# Schematic_2023-04-17.net
KiCad netlist of a schematic drawn in Altium Designer
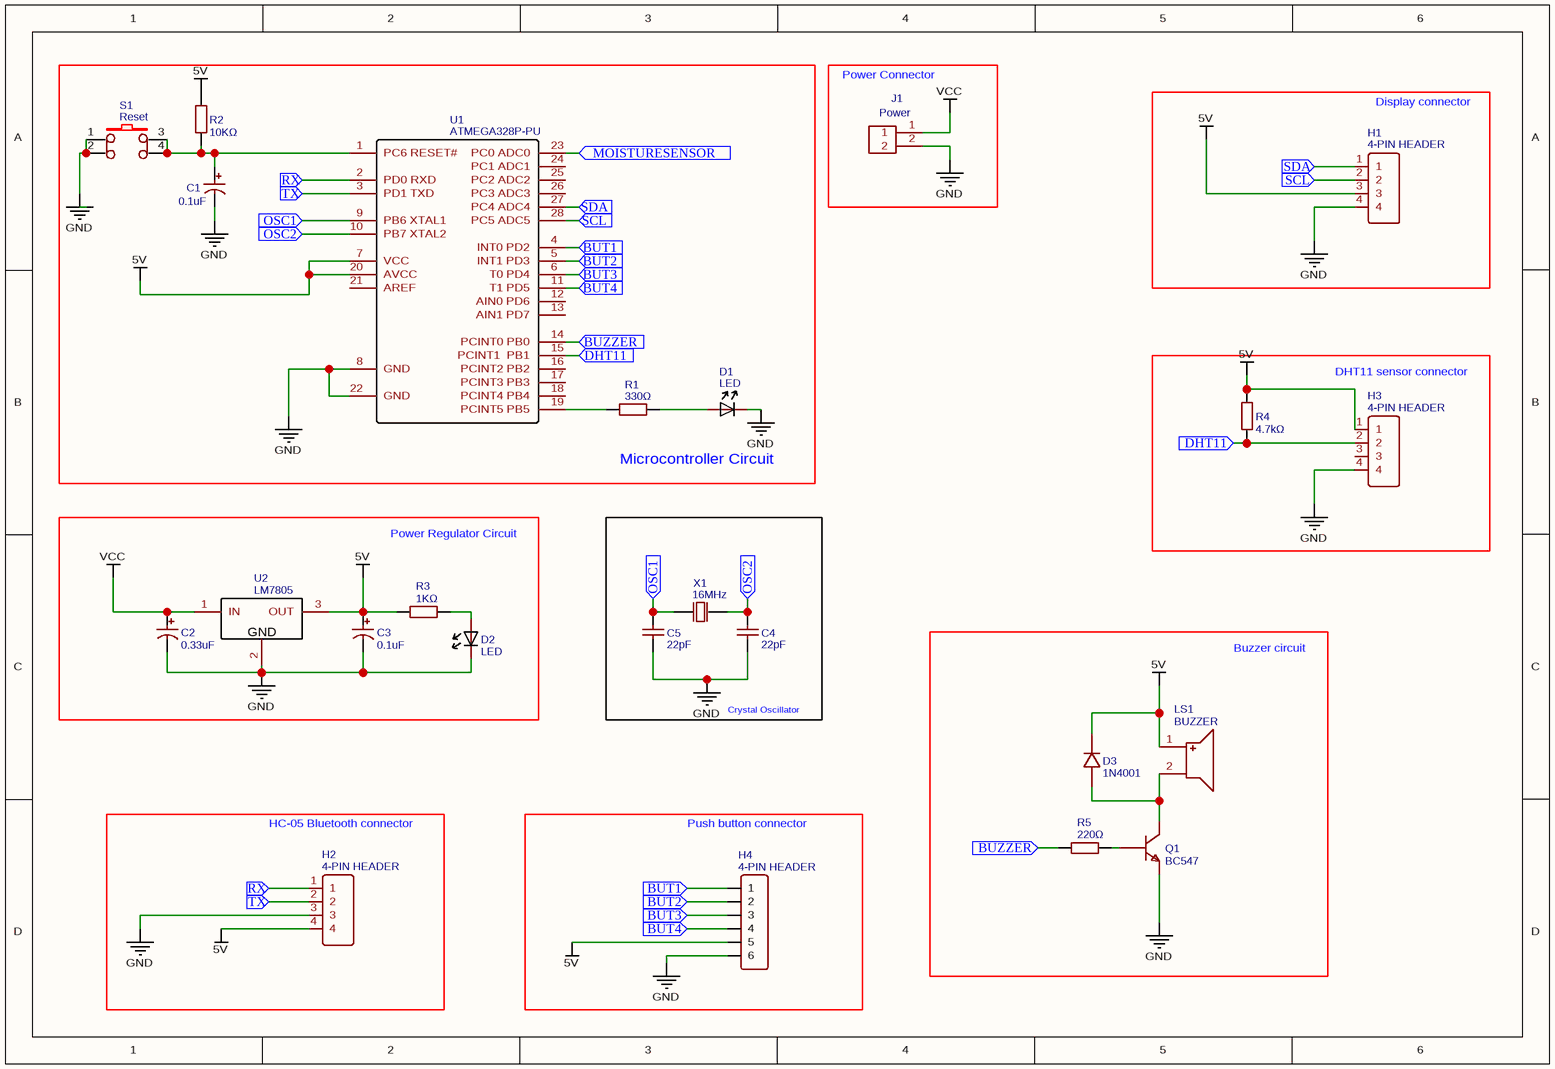
[diagram p0: Schematic_2023-04-17.schdoc]

(export (version "E")
  (design (tool "Eeschema 10.0.6"))
  (components
    (comp (ref "C1")
      (value "0.1uF")
      (fields (field (name "BOM_MANUFACTURER PART") "0.1UF 50V") (field (name "BOM_SUPPLIER PART") "C28061"))
      (libsource (lib "altium-import") (part "root_0_0.1uF_"))
    )
    (comp (ref "C2")
      (value "0.33uF")
      (fields
        (field (name "BOM_MANUFACTURER PART") "0.33uF 50V 5*11")
        (field (name "BOM_SUPPLIER PART") "C45097")
      )
      (libsource (lib "altium-import") (part "root_0_0.33uF_"))
    )
    (comp (ref "C3")
      (value "0.1uF")
      (fields (field (name "BOM_MANUFACTURER PART") "0.1UF 50V") (field (name "BOM_SUPPLIER PART") "C28061"))
      (libsource (lib "altium-import") (part "root_0_0.1uF_"))
    )
    (comp (ref "C4")
      (value "22pF")
      (fields
        (field (name "BOM_MANUFACTURER PART") "22pf/50V 10%")
        (field (name "BOM_SUPPLIER PART") "C9316")
      )
      (libsource (lib "altium-import") (part "root_3_22pF_"))
    )
    (comp (ref "C5")
      (value "22pF")
      (fields
        (field (name "BOM_MANUFACTURER PART") "22pf/50V 10%")
        (field (name "BOM_SUPPLIER PART") "C9316")
      )
      (libsource (lib "altium-import") (part "root_3_22pF_"))
    )
    (comp (ref "D1")
      (value "LED")
      (fields (field (name "BOM_MANUFACTURER PART") "5mm LED") (field (name "CONTRIBUTOR") "Axbri"))
      (libsource (lib "altium-import") (part "root_0_LED_"))
    )
    (comp (ref "D2")
      (value "LED")
      (fields (field (name "BOM_MANUFACTURER PART") "5mm LED") (field (name "CONTRIBUTOR") "Axbri"))
      (libsource (lib "altium-import") (part "root_3_LED_"))
    )
    (comp (ref "D3")
      (value "1N4001")
      (fields (field (name "BOM_SUPPLIER PART") "C99656") (field (name "CONTRIBUTOR") "LCSC"))
      (libsource (lib "altium-import") (part "root_3_1N4001_"))
    )
    (comp (ref "H1")
      (value "4-PIN HEADER")
      (fields (field (name "CONTRIBUTOR") "Kang Yi Te"))
      (libsource (lib "altium-import") (part "root_0_4-PIN HEADER_"))
    )
    (comp (ref "H2")
      (value "4-PIN HEADER")
      (fields (field (name "CONTRIBUTOR") "Kang Yi Te"))
      (libsource (lib "altium-import") (part "root_0_4-PIN HEADER_"))
    )
    (comp (ref "H3")
      (value "4-PIN HEADER")
      (fields (field (name "CONTRIBUTOR") "Kang Yi Te"))
      (libsource (lib "altium-import") (part "root_0_4-PIN HEADER_"))
    )
    (comp (ref "H4")
      (value "4-PIN HEADER")
      (fields (field (name "BOM_SUPPLIER PART") "C40877") (field (name "CONTRIBUTOR") "LCEDA_Lib"))
      (libsource (lib "") (part "root_0_4-PIN HEADER__1"))
    )
    (comp (ref "J1")
      (value "Power")
      (fields
        (field (name "BOM_MANUFACTURER PART") "XHB-2A Connector")
        (field (name "BOM_SUPPLIER PART") "C57981")
      )
      (libsource (lib "altium-import") (part "root_0_Power_"))
    )
    (comp (ref "LS1")
      (value "BUZZER")
      (fields
        (field (name "BOM_MANUFACTURER PART") "BUZZERHMB1206-03")
        (field (name "BOM_SUPPLIER PART") "C96101")
        (field (name "CONTRIBUTOR") "วริศรา เกรียงไกรวัฒน์ /ทิพพะ")
      )
      (libsource (lib "altium-import") (part "root_0_BUZZER_"))
    )
    (comp (ref "Q1")
      (value "BC547")
      (fields
        (field (name "BOM_SUPPLIER PART") "C900798")
        (field (name "BOM_MANUFACTURER PART") "BC547BTF")
        (field (name "CONTRIBUTOR") "LCSC")
      )
      (libsource (lib "altium-import") (part "root_0_BC547_"))
    )
    (comp (ref "R1")
      (value "330Ω")
      (fields
        (field (name "POWER") "1/4W")
        (field (name "TOLERANCE") "±1%")
        (field (name "BOM_SUPPLIER PART") "E57439")
      )
      (libsource (lib "altium-import") (part "root_0_330Ω_"))
    )
    (comp (ref "R2")
      (value "10KΩ")
      (fields
        (field (name "POWER") "1/4W")
        (field (name "TOLERANCE") "±1%")
        (field (name "BOM_SUPPLIER PART") "E57439")
      )
      (libsource (lib "altium-import") (part "root_3_10KΩ_"))
    )
    (comp (ref "R3")
      (value "1KΩ")
      (fields
        (field (name "POWER") "1/4W")
        (field (name "TOLERANCE") "±1%")
        (field (name "BOM_SUPPLIER PART") "E57439")
      )
      (libsource (lib "altium-import") (part "root_0_1KΩ_"))
    )
    (comp (ref "R4")
      (value "4.7kΩ")
      (fields
        (field (name "POWER") "1/4W")
        (field (name "TOLERANCE") "±1%")
        (field (name "BOM_SUPPLIER PART") "E57439")
      )
      (libsource (lib "altium-import") (part "root_3_4.7kΩ_"))
    )
    (comp (ref "R5")
      (value "220Ω")
      (fields
        (field (name "POWER") "1/4W")
        (field (name "TOLERANCE") "±1%")
        (field (name "BOM_SUPPLIER PART") "E57439")
      )
      (libsource (lib "altium-import") (part "root_0_220Ω_"))
    )
    (comp (ref "S1")
      (value "Reset")
      (fields
        (field (name "BOM_SUPPLIER PART") "C59980")
        (field (name "BOM_MANUFACTURER PART") "button6*6*8.5")
      )
      (libsource (lib "altium-import") (part "root_0_Reset_"))
    )
    (comp (ref "U1")
      (value "ATMEGA328P-PU")
      (fields (field (name "BOM_SUPPLIER PART") "C33901") (field (name "CONTRIBUTOR") "LCSC"))
      (libsource (lib "altium-import") (part "root_0_ATMEGA328P-PU_"))
    )
    (comp (ref "U2")
      (value "LM7805")
      (fields
        (field (name "BOM_MANUFACTURER PART") "L7805CV-DG")
        (field (name "BOM_SUPPLIER PART") "C3795")
        (field (name "CONTRIBUTOR") "LCEDA_Lib")
      )
      (libsource (lib "altium-import") (part "root_0_LM7805_"))
    )
    (comp (ref "X1")
      (value "16MHz")
      (fields
        (field (name "BOM_SUPPLIER PART") "C1669847")
        (field (name "BOM_MANUFACTURER PART") "ATS16A")
        (field (name "CONTRIBUTOR") "lcsc")
      )
      (libsource (lib "altium-import") (part "root_0_16MHz_"))
    )
  )
  (nets
    (net (code "1") (name "/BUT1") (class "Default")
      (node (ref "H4") (pin "1") (pinfunction "1_1") (pintype "passive"))
      (node (ref "U1") (pin "4") (pinfunction "INT0_PD2_4") (pintype "passive"))
    )
    (net (code "2") (name "/BUT2") (class "Default")
      (node (ref "H4") (pin "2") (pinfunction "2_2") (pintype "passive"))
      (node (ref "U1") (pin "5") (pinfunction "INT1_PD3_5") (pintype "passive"))
    )
    (net (code "3") (name "/BUT3") (class "Default")
      (node (ref "H4") (pin "3") (pinfunction "3_3") (pintype "passive"))
      (node (ref "U1") (pin "6") (pinfunction "T0_PD4_6") (pintype "passive"))
    )
    (net (code "4") (name "/BUT4") (class "Default")
      (node (ref "H4") (pin "4") (pinfunction "4_4") (pintype "passive"))
      (node (ref "U1") (pin "11") (pinfunction "T1_PD5_11") (pintype "passive"))
    )
    (net (code "5") (name "/BUZZER") (class "Default")
      (node (ref "R5") (pin "1") (pinfunction "1_1") (pintype "passive"))
      (node (ref "U1") (pin "14") (pinfunction "PCINT0_PB0_14") (pintype "passive"))
    )
    (net (code "6") (name "/DHT11") (class "Default")
      (node (ref "H3") (pin "2") (pinfunction "2_2") (pintype "passive"))
      (node (ref "R4") (pin "2") (pinfunction "2_2") (pintype "passive"))
      (node (ref "U1") (pin "15") (pinfunction "PCINT1__PB1_15") (pintype "passive"))
    )
    (net (code "7") (name "/MOISTURESENSOR") (class "Default")
      (node (ref "U1") (pin "23") (pinfunction "PC0_ADC0_23") (pintype "passive"))
    )
    (net (code "8") (name "/OSC1") (class "Default")
      (node (ref "C5") (pin "1") (pinfunction "1_1") (pintype "passive"))
      (node (ref "U1") (pin "9") (pinfunction "PB6_XTAL1_9") (pintype "passive"))
      (node (ref "X1") (pin "1") (pinfunction "1_1") (pintype "passive"))
    )
    (net (code "9") (name "/OSC2") (class "Default")
      (node (ref "C4") (pin "1") (pinfunction "1_1") (pintype "passive"))
      (node (ref "U1") (pin "10") (pinfunction "PB7_XTAL2_10") (pintype "passive"))
      (node (ref "X1") (pin "2") (pinfunction "2_2") (pintype "passive"))
    )
    (net (code "10") (name "/RX") (class "Default")
      (node (ref "H2") (pin "1") (pinfunction "1_1") (pintype "passive"))
      (node (ref "U1") (pin "2") (pinfunction "PD0_RXD_2") (pintype "passive"))
    )
    (net (code "11") (name "/SCL") (class "Default")
      (node (ref "H1") (pin "2") (pinfunction "2_2") (pintype "passive"))
      (node (ref "U1") (pin "28") (pinfunction "PC5_ADC5_28") (pintype "passive"))
    )
    (net (code "12") (name "/SDA") (class "Default")
      (node (ref "H1") (pin "1") (pinfunction "1_1") (pintype "passive"))
      (node (ref "U1") (pin "27") (pinfunction "PC4_ADC4_27") (pintype "passive"))
    )
    (net (code "13") (name "/TX") (class "Default")
      (node (ref "H2") (pin "2") (pinfunction "2_2") (pintype "passive"))
      (node (ref "U1") (pin "3") (pinfunction "PD1_TXD_3") (pintype "passive"))
    )
    (net (code "14") (name "5V") (class "Default")
      (node (ref "C3") (pin "1") (pinfunction "1_1") (pintype "passive"))
      (node (ref "D3") (pin "1") (pinfunction "C_1") (pintype "passive"))
      (node (ref "H1") (pin "3") (pinfunction "3_3") (pintype "passive"))
      (node (ref "H2") (pin "4") (pinfunction "4_4") (pintype "passive"))
      (node (ref "H3") (pin "1") (pinfunction "1_1") (pintype "passive"))
      (node (ref "H4") (pin "5") (pinfunction "5_5") (pintype "passive"))
      (node (ref "LS1") (pin "1") (pinfunction "1_1") (pintype "passive"))
      (node (ref "R2") (pin "1") (pinfunction "1_1") (pintype "passive"))
      (node (ref "R3") (pin "1") (pinfunction "1_1") (pintype "passive"))
      (node (ref "R4") (pin "1") (pinfunction "1_1") (pintype "passive"))
      (node (ref "U1") (pin "20") (pinfunction "AVCC_20") (pintype "passive"))
      (node (ref "U1") (pin "7") (pinfunction "VCC_7") (pintype "passive"))
      (node (ref "U2") (pin "3") (pinfunction "OUT_3") (pintype "passive"))
    )
    (net (code "15") (name "GND") (class "Default")
      (node (ref "C1") (pin "2") (pinfunction "2_2") (pintype "passive"))
      (node (ref "C2") (pin "2") (pinfunction "2_2") (pintype "passive"))
      (node (ref "C3") (pin "2") (pinfunction "2_2") (pintype "passive"))
      (node (ref "C4") (pin "2") (pinfunction "2_2") (pintype "passive"))
      (node (ref "C5") (pin "2") (pinfunction "2_2") (pintype "passive"))
      (node (ref "D1") (pin "2") (pinfunction "2_2") (pintype "passive"))
      (node (ref "D2") (pin "2") (pinfunction "2_2") (pintype "passive"))
      (node (ref "H1") (pin "4") (pinfunction "4_4") (pintype "passive"))
      (node (ref "H2") (pin "3") (pinfunction "3_3") (pintype "passive"))
      (node (ref "H3") (pin "4") (pinfunction "4_4") (pintype "passive"))
      (node (ref "H4") (pin "6") (pinfunction "6_6") (pintype "passive"))
      (node (ref "J1") (pin "2") (pinfunction "2_2") (pintype "passive"))
      (node (ref "Q1") (pin "3") (pinfunction "E_3") (pintype "passive"))
      (node (ref "S1") (pin "1") (pinfunction "1_1") (pintype "passive"))
      (node (ref "S1") (pin "2") (pinfunction "2_2") (pintype "passive"))
      (node (ref "U1") (pin "22") (pinfunction "GND_22") (pintype "passive"))
      (node (ref "U1") (pin "8") (pinfunction "GND_8") (pintype "passive"))
      (node (ref "U2") (pin "2") (pinfunction "GND_2") (pintype "passive"))
    )
    (net (code "16") (name "Net-(D1-Pad1)") (class "Default")
      (node (ref "D1") (pin "1") (pinfunction "1_1") (pintype "passive"))
      (node (ref "R1") (pin "2") (pinfunction "2_2") (pintype "passive"))
    )
    (net (code "17") (name "Net-(D2-Pad1)") (class "Default")
      (node (ref "D2") (pin "1") (pinfunction "1_1") (pintype "passive"))
      (node (ref "R3") (pin "2") (pinfunction "2_2") (pintype "passive"))
    )
    (net (code "18") (name "Net-(D3-A)") (class "Default")
      (node (ref "D3") (pin "2") (pinfunction "A_2") (pintype "passive"))
      (node (ref "LS1") (pin "2") (pinfunction "2_2") (pintype "passive"))
      (node (ref "Q1") (pin "1") (pinfunction "C_1") (pintype "passive"))
    )
    (net (code "19") (name "Net-(Q1-B)") (class "Default")
      (node (ref "Q1") (pin "2") (pinfunction "B_2") (pintype "passive"))
      (node (ref "R5") (pin "2") (pinfunction "2_2") (pintype "passive"))
    )
    (net (code "20") (name "Net-(U1-PC6_RESET#)") (class "Default")
      (node (ref "C1") (pin "1") (pinfunction "1_1") (pintype "passive"))
      (node (ref "R2") (pin "2") (pinfunction "2_2") (pintype "passive"))
      (node (ref "S1") (pin "3") (pinfunction "3_3") (pintype "passive"))
      (node (ref "S1") (pin "4") (pinfunction "4_4") (pintype "passive"))
      (node (ref "U1") (pin "1") (pinfunction "PC6_RESET#_1") (pintype "passive"))
    )
    (net (code "21") (name "Net-(U1-PCINT5_PB5)") (class "Default")
      (node (ref "R1") (pin "1") (pinfunction "1_1") (pintype "passive"))
      (node (ref "U1") (pin "19") (pinfunction "PCINT5_PB5_19") (pintype "passive"))
    )
    (net (code "22") (name "VCC") (class "Default")
      (node (ref "C2") (pin "1") (pinfunction "1_1") (pintype "passive"))
      (node (ref "J1") (pin "1") (pinfunction "1_1") (pintype "passive"))
      (node (ref "U2") (pin "1") (pinfunction "IN_1") (pintype "passive"))
    )
    (net (code "23") (name "unconnected-(H3-Pad3)") (class "Default")
      (node (ref "H3") (pin "3") (pinfunction "3_3") (pintype "passive"))
    )
    (net (code "24") (name "unconnected-(U1-AIN0_PD6-Pad12)") (class "Default")
      (node (ref "U1") (pin "12") (pinfunction "AIN0_PD6_12") (pintype "passive"))
    )
    (net (code "25") (name "unconnected-(U1-AIN1_PD7-Pad13)") (class "Default")
      (node (ref "U1") (pin "13") (pinfunction "AIN1_PD7_13") (pintype "passive"))
    )
    (net (code "26") (name "unconnected-(U1-AREF-Pad21)") (class "Default")
      (node (ref "U1") (pin "21") (pinfunction "AREF_21") (pintype "passive"))
    )
    (net (code "27") (name "unconnected-(U1-PC1_ADC1-Pad24)") (class "Default")
      (node (ref "U1") (pin "24") (pinfunction "PC1_ADC1_24") (pintype "passive"))
    )
    (net (code "28") (name "unconnected-(U1-PC2_ADC2-Pad25)") (class "Default")
      (node (ref "U1") (pin "25") (pinfunction "PC2_ADC2_25") (pintype "passive"))
    )
    (net (code "29") (name "unconnected-(U1-PC3_ADC3-Pad26)") (class "Default")
      (node (ref "U1") (pin "26") (pinfunction "PC3_ADC3_26") (pintype "passive"))
    )
    (net (code "30") (name "unconnected-(U1-PCINT2_PB2-Pad16)") (class "Default")
      (node (ref "U1") (pin "16") (pinfunction "PCINT2_PB2_16") (pintype "passive"))
    )
    (net (code "31") (name "unconnected-(U1-PCINT3_PB3-Pad17)") (class "Default")
      (node (ref "U1") (pin "17") (pinfunction "PCINT3_PB3_17") (pintype "passive"))
    )
    (net (code "32") (name "unconnected-(U1-PCINT4_PB4-Pad18)") (class "Default")
      (node (ref "U1") (pin "18") (pinfunction "PCINT4_PB4_18") (pintype "passive"))
    )
  )
)
